# Liion-Tester.net
KiCad netlist of a schematic drawn in EAGLE
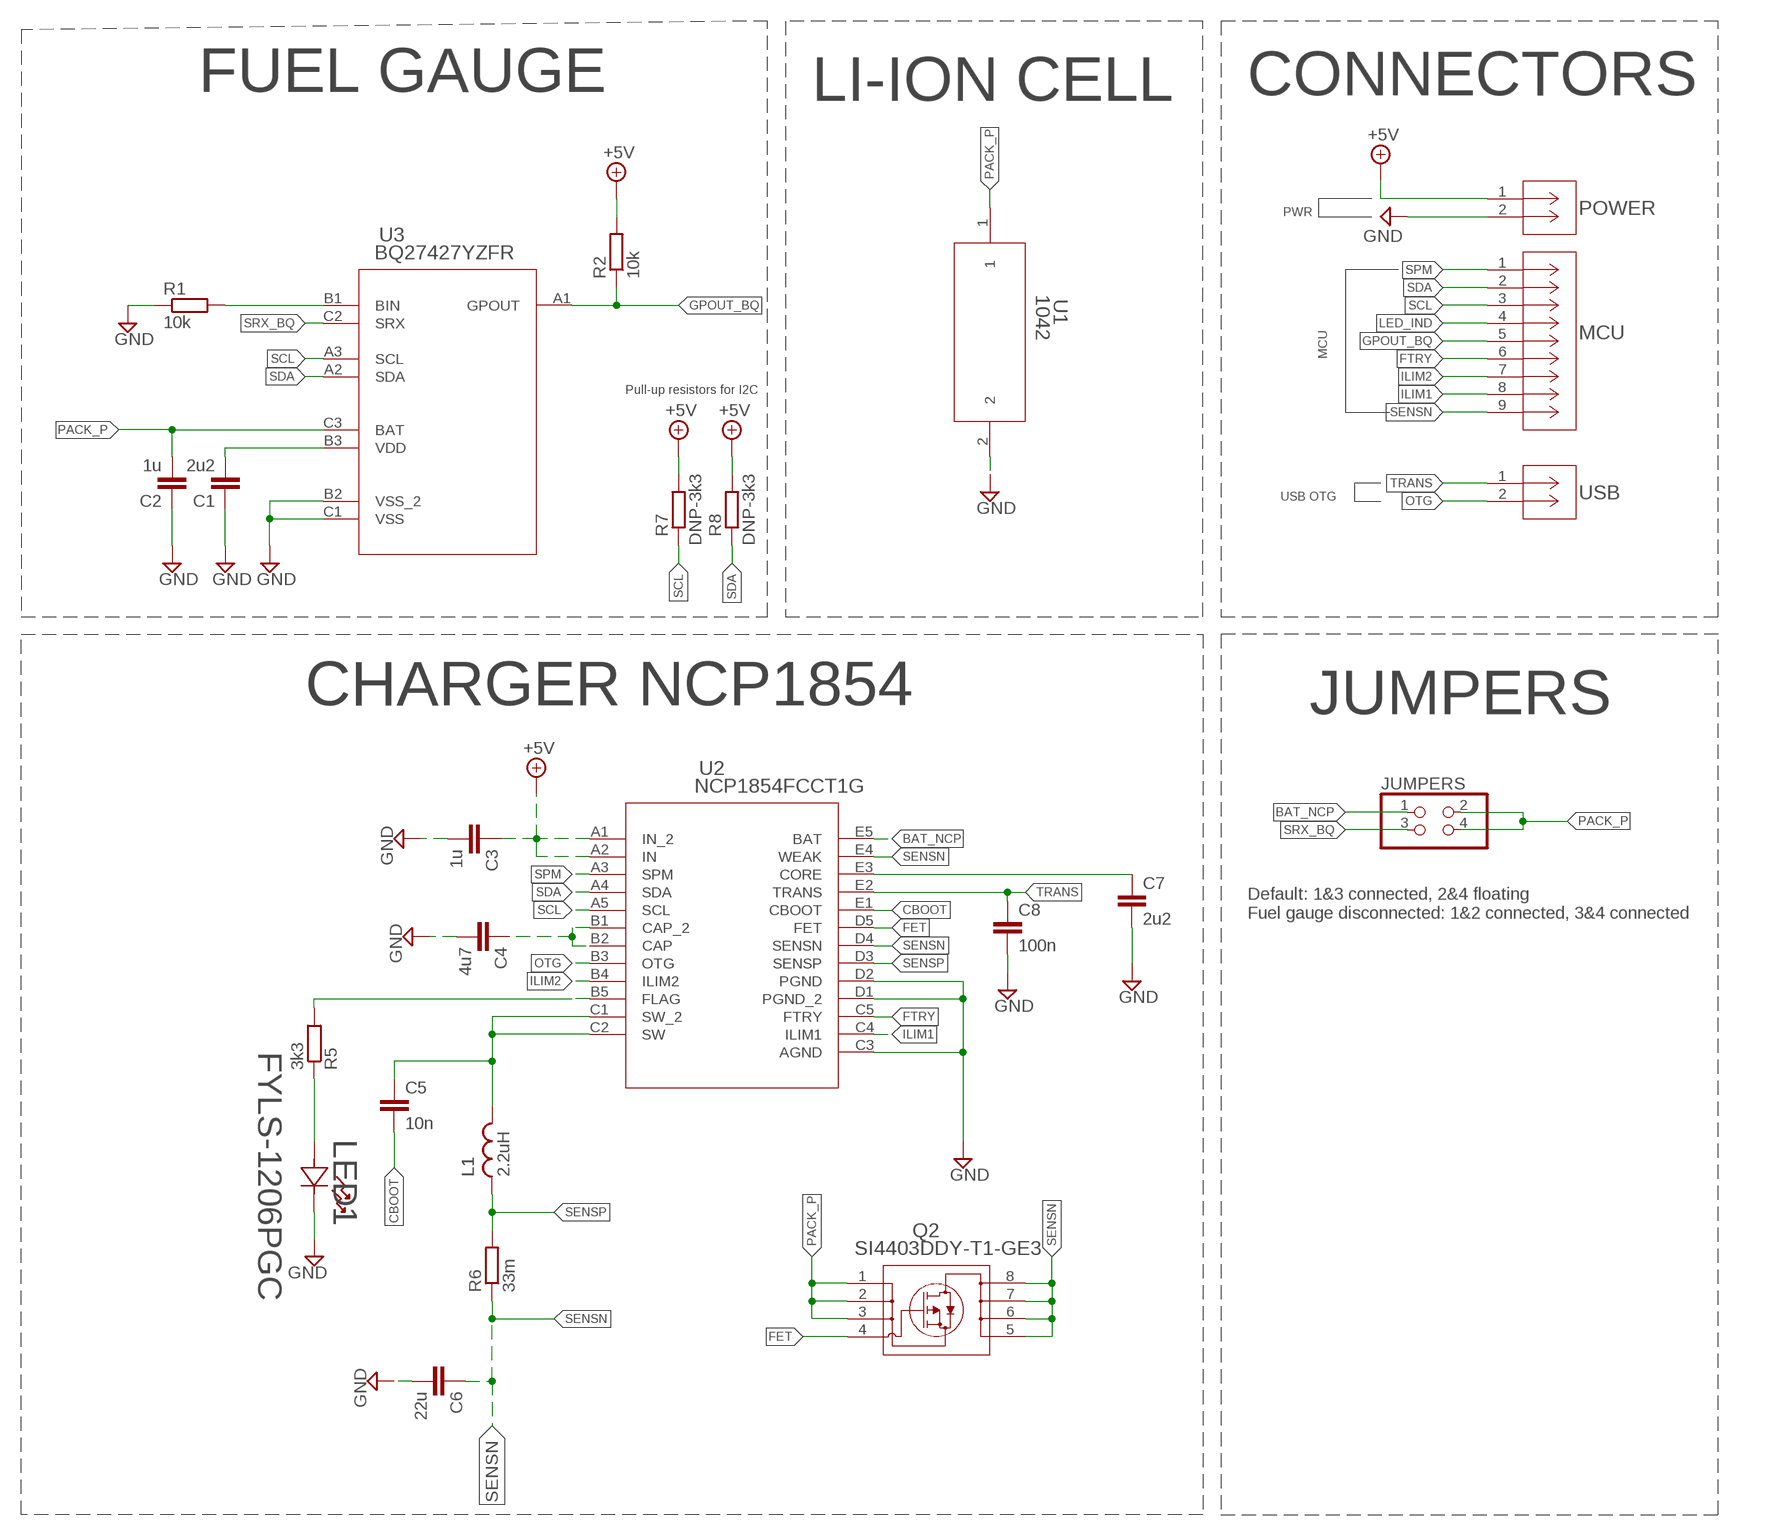
[diagram p0: schematic, sheet 1]

(export (version "E")
  (design (tool "Eeschema 10.0.6"))
  (components
    (comp (ref "C1")
      (value "2u2")
      (footprint "eagle-import:C0603")
      (libsource (lib "eagle-import") (part "C-EUC0603"))
    )
    (comp (ref "C2")
      (value "1u")
      (footprint "eagle-import:C0603")
      (libsource (lib "eagle-import") (part "C-EUC0603"))
    )
    (comp (ref "C3")
      (value "1u")
      (footprint "eagle-import:C0603")
      (libsource (lib "eagle-import") (part "C-EUC0603"))
    )
    (comp (ref "C4")
      (value "4u7")
      (footprint "eagle-import:C0603")
      (libsource (lib "eagle-import") (part "C-EUC0603"))
    )
    (comp (ref "C5")
      (value "10n")
      (footprint "eagle-import:C0603")
      (libsource (lib "eagle-import") (part "C-EUC0603"))
    )
    (comp (ref "C6")
      (value "22u")
      (footprint "eagle-import:C0603")
      (libsource (lib "eagle-import") (part "C-EUC0603"))
    )
    (comp (ref "C7")
      (value "2u2")
      (footprint "eagle-import:C0603")
      (libsource (lib "eagle-import") (part "C-EUC0603"))
    )
    (comp (ref "C8")
      (value "100n")
      (footprint "eagle-import:C0603")
      (libsource (lib "eagle-import") (part "C-EUC0603"))
    )
    (comp (ref "JUMPERS")
      (value "PINHD-2X2")
      (footprint "eagle-import:2X02")
      (libsource (lib "eagle-import") (part "PINHD-2X2"))
    )
    (comp (ref "L1")
      (value "2.2uH")
      (footprint "eagle-import:SPM3012T-2R2M-LR")
      (libsource (lib "eagle-import") (part "SPM3012T-2R2M-LR"))
    )
    (comp (ref "LED1")
      (value "FYLS-1206PGC")
      (footprint "eagle-import:LED_QBLP650_1206_QTB")
      (fields
        (field (name "MANUFACTURER_PART_NUMBER") "QBLP650-IW")
        (field (name "COPYRIGHT") "Copyright (C) 2024 Ultra Librarian. All rights reserved.")
      )
      (libsource (lib "eagle-import") (part "QBLP650-IW"))
    )
    (comp (ref "MCU")
      (value "250-109")
      (footprint "eagle-import:CONN_250-109_WAG")
      (fields (field (name "COPYRIGHT") "Copyright (C) 2024 Ultra Librarian. All rights reserved."))
      (libsource (lib "eagle-import") (part "250-109"))
    )
    (comp (ref "POWER")
      (value "250-102")
      (footprint "eagle-import:CONN_250-102_WAG")
      (fields (field (name "COPYRIGHT") "Copyright (C) 2024 Ultra Librarian. All rights reserved."))
      (libsource (lib "eagle-import") (part "250-102"))
    )
    (comp (ref "Q2")
      (value "SI4403DDY-T1-GE3")
      (footprint "eagle-import:SO-8_MS-012_VIS")
      (fields (field (name "COPYRIGHT") "Copyright (C) 2024 Ultra Librarian. All rights reserved."))
      (libsource (lib "eagle-import") (part "SI4403DDY-T1-GE3"))
    )
    (comp (ref "R1")
      (value "10k")
      (footprint "eagle-import:R0603")
      (libsource (lib "eagle-import") (part "R-EU_R0603"))
    )
    (comp (ref "R2")
      (value "10k")
      (footprint "eagle-import:R0603")
      (libsource (lib "eagle-import") (part "R-EU_R0603"))
    )
    (comp (ref "R5")
      (value "3k3")
      (footprint "eagle-import:R0603")
      (libsource (lib "eagle-import") (part "R-EU_R0603"))
    )
    (comp (ref "R6")
      (value "33m")
      (footprint "eagle-import:R2512")
      (libsource (lib "eagle-import") (part "R-EU_R2512"))
    )
    (comp (ref "R7")
      (value "DNP-3k3")
      (footprint "eagle-import:R0603")
      (libsource (lib "eagle-import") (part "R-EU_R0603"))
    )
    (comp (ref "R8")
      (value "DNP-3k3")
      (footprint "eagle-import:R0603")
      (libsource (lib "eagle-import") (part "R-EU_R0603"))
    )
    (comp (ref "U1")
      (value "1042")
      (footprint "eagle-import:1042_KEY")
      (fields (field (name "COPYRIGHT") "Copyright (C) 2024 Ultra Librarian. All rights reserved."))
      (libsource (lib "eagle-import") (part "1042"))
    )
    (comp (ref "U2")
      (value "NCP1854FCCT1G")
      (footprint "eagle-import:BGA25_2P55X2P2_ONS")
      (fields (field (name "COPYRIGHT") "Copyright (C) 2024 Ultra Librarian. All rights reserved."))
      (libsource (lib "eagle-import") (part "NCP1854FCCT1G"))
    )
    (comp (ref "U3")
      (value "BQ27427YZFR")
      (footprint "eagle-import:DSBGA9-YZF_TEX")
      (fields (field (name "COPYRIGHT") "Copyright (C) 2024 Ultra Librarian. All rights reserved."))
      (libsource (lib "eagle-import") (part "BQ27427YZFR"))
    )
    (comp (ref "USB")
      (value "250-102")
      (footprint "eagle-import:CONN_250-102_WAG")
      (fields (field (name "COPYRIGHT") "Copyright (C) 2024 Ultra Librarian. All rights reserved."))
      (libsource (lib "eagle-import") (part "250-102"))
    )
  )
  (nets
    (net (code "1") (name "+5V") (class "Default")
      (node (ref "C3") (pin "1") (pinfunction "1_1") (pintype "passive"))
      (node (ref "POWER") (pin "1") (pinfunction "1_1") (pintype "passive"))
      (node (ref "R2") (pin "2") (pinfunction "2_2") (pintype "passive"))
      (node (ref "R7") (pin "2") (pinfunction "2_2") (pintype "passive"))
      (node (ref "R8") (pin "2") (pinfunction "2_2") (pintype "passive"))
      (node (ref "U2") (pin "A1") (pinfunction "IN_2_A1") (pintype "input"))
      (node (ref "U2") (pin "A2") (pinfunction "IN_A2") (pintype "input"))
    )
    (net (code "2") (name "BAT_NCP") (class "Default")
      (node (ref "JUMPERS") (pin "1") (pinfunction "1_1") (pintype "passive"))
      (node (ref "U2") (pin "E5") (pinfunction "BAT_E5") (pintype "input"))
    )
    (net (code "3") (name "CBOOT") (class "Default")
      (node (ref "C5") (pin "2") (pinfunction "2_2") (pintype "passive"))
      (node (ref "U2") (pin "E1") (pinfunction "CBOOT_E1") (pintype "bidirectional"))
    )
    (net (code "4") (name "FET") (class "Default")
      (node (ref "Q2") (pin "4") (pinfunction "4_4") (pintype "passive"))
      (node (ref "U2") (pin "D5") (pinfunction "FET_D5") (pintype "output"))
    )
    (net (code "5") (name "FTRY") (class "Default")
      (node (ref "MCU") (pin "6") (pinfunction "6_6") (pintype "passive"))
      (node (ref "U2") (pin "C5") (pinfunction "FTRY_C5") (pintype "input"))
    )
    (net (code "6") (name "GND") (class "Default")
      (node (ref "C1") (pin "1") (pinfunction "1_1") (pintype "passive"))
      (node (ref "C2") (pin "1") (pinfunction "1_1") (pintype "passive"))
      (node (ref "C3") (pin "2") (pinfunction "2_2") (pintype "passive"))
      (node (ref "C4") (pin "2") (pinfunction "2_2") (pintype "passive"))
      (node (ref "C6") (pin "2") (pinfunction "2_2") (pintype "passive"))
      (node (ref "C7") (pin "2") (pinfunction "2_2") (pintype "passive"))
      (node (ref "C8") (pin "2") (pinfunction "2_2") (pintype "passive"))
      (node (ref "LED1") (pin "1") (pinfunction "CATHODE_1") (pintype "passive"))
      (node (ref "POWER") (pin "2") (pinfunction "2_2") (pintype "passive"))
      (node (ref "R1") (pin "1") (pinfunction "1_1") (pintype "passive"))
      (node (ref "U1") (pin "2") (pinfunction "2_2") (pintype "passive"))
      (node (ref "U2") (pin "C3") (pinfunction "AGND_C3") (pintype "power_in"))
      (node (ref "U2") (pin "D1") (pinfunction "PGND_2_D1") (pintype "power_in"))
      (node (ref "U2") (pin "D2") (pinfunction "PGND_D2") (pintype "power_in"))
      (node (ref "U3") (pin "B2") (pinfunction "VSS_2_B2") (pintype "passive"))
      (node (ref "U3") (pin "C1") (pinfunction "VSS_C1") (pintype "passive"))
    )
    (net (code "7") (name "GPOUT_BQ") (class "Default")
      (node (ref "MCU") (pin "5") (pinfunction "5_5") (pintype "passive"))
      (node (ref "R2") (pin "1") (pinfunction "1_1") (pintype "passive"))
      (node (ref "U3") (pin "A1") (pinfunction "GPOUT_A1") (pintype "output"))
    )
    (net (code "8") (name "ILIM1") (class "Default")
      (node (ref "MCU") (pin "8") (pinfunction "8_8") (pintype "passive"))
      (node (ref "U2") (pin "C4") (pinfunction "ILIM1_C4") (pintype "input"))
    )
    (net (code "9") (name "ILIM2") (class "Default")
      (node (ref "MCU") (pin "7") (pinfunction "7_7") (pintype "passive"))
      (node (ref "U2") (pin "B4") (pinfunction "ILIM2_B4") (pintype "input"))
    )
    (net (code "10") (name "LED_IND") (class "Default")
      (node (ref "MCU") (pin "4") (pinfunction "4_4") (pintype "passive"))
      (node (ref "R5") (pin "2") (pinfunction "2_2") (pintype "passive"))
      (node (ref "U2") (pin "B5") (pinfunction "FLAG_B5") (pintype "output"))
    )
    (net (code "11") (name "Net-(L1-2)") (class "Default")
      (node (ref "C5") (pin "1") (pinfunction "1_1") (pintype "passive"))
      (node (ref "L1") (pin "P$2") (pinfunction "2_P$2") (pintype "passive"))
      (node (ref "U2") (pin "C1") (pinfunction "SW_2_C1") (pintype "output"))
      (node (ref "U2") (pin "C2") (pinfunction "SW_C2") (pintype "output"))
    )
    (net (code "12") (name "Net-(LED1-ANODE)") (class "Default")
      (node (ref "LED1") (pin "2") (pinfunction "ANODE_2") (pintype "passive"))
      (node (ref "R5") (pin "1") (pinfunction "1_1") (pintype "passive"))
    )
    (net (code "13") (name "Net-(U2-CAP)") (class "Default")
      (node (ref "C4") (pin "1") (pinfunction "1_1") (pintype "passive"))
      (node (ref "U2") (pin "B1") (pinfunction "CAP_2_B1") (pintype "passive"))
      (node (ref "U2") (pin "B2") (pinfunction "CAP_B2") (pintype "passive"))
    )
    (net (code "14") (name "Net-(U2-CORE)") (class "Default")
      (node (ref "C7") (pin "1") (pinfunction "1_1") (pintype "passive"))
      (node (ref "U2") (pin "E3") (pinfunction "CORE_E3") (pintype "output"))
    )
    (net (code "15") (name "Net-(U3-BIN)") (class "Default")
      (node (ref "R1") (pin "2") (pinfunction "2_2") (pintype "passive"))
      (node (ref "U3") (pin "B1") (pinfunction "BIN_B1") (pintype "input"))
    )
    (net (code "16") (name "Net-(U3-VDD)") (class "Default")
      (node (ref "C1") (pin "2") (pinfunction "2_2") (pintype "passive"))
      (node (ref "U3") (pin "B3") (pinfunction "VDD_B3") (pintype "output"))
    )
    (net (code "17") (name "OTG") (class "Default")
      (node (ref "U2") (pin "B3") (pinfunction "OTG_B3") (pintype "input"))
      (node (ref "USB") (pin "2") (pinfunction "2_2") (pintype "passive"))
    )
    (net (code "18") (name "PACK_P") (class "Default")
      (node (ref "C2") (pin "2") (pinfunction "2_2") (pintype "passive"))
      (node (ref "JUMPERS") (pin "2") (pinfunction "2_2") (pintype "passive"))
      (node (ref "JUMPERS") (pin "4") (pinfunction "4_4") (pintype "passive"))
      (node (ref "Q2") (pin "1") (pinfunction "1_1") (pintype "passive"))
      (node (ref "Q2") (pin "2") (pinfunction "2_2") (pintype "passive"))
      (node (ref "Q2") (pin "3") (pinfunction "3_3") (pintype "passive"))
      (node (ref "U1") (pin "1") (pinfunction "1_1") (pintype "passive"))
      (node (ref "U3") (pin "C3") (pinfunction "BAT_C3") (pintype "power_in"))
    )
    (net (code "19") (name "SCL") (class "Default")
      (node (ref "MCU") (pin "3") (pinfunction "3_3") (pintype "passive"))
      (node (ref "R7") (pin "1") (pinfunction "1_1") (pintype "passive"))
      (node (ref "U2") (pin "A5") (pinfunction "SCL_A5") (pintype "input"))
      (node (ref "U3") (pin "A3") (pinfunction "SCL_A3") (pintype "bidirectional"))
    )
    (net (code "20") (name "SDA") (class "Default")
      (node (ref "MCU") (pin "2") (pinfunction "2_2") (pintype "passive"))
      (node (ref "R8") (pin "1") (pinfunction "1_1") (pintype "passive"))
      (node (ref "U2") (pin "A4") (pinfunction "SDA_A4") (pintype "bidirectional"))
      (node (ref "U3") (pin "A2") (pinfunction "SDA_A2") (pintype "bidirectional"))
    )
    (net (code "21") (name "SENSN") (class "Default")
      (node (ref "C6") (pin "1") (pinfunction "1_1") (pintype "passive"))
      (node (ref "MCU") (pin "9") (pinfunction "9_9") (pintype "passive"))
      (node (ref "Q2") (pin "5") (pinfunction "5_5") (pintype "passive"))
      (node (ref "Q2") (pin "6") (pinfunction "6_6") (pintype "passive"))
      (node (ref "Q2") (pin "7") (pinfunction "7_7") (pintype "passive"))
      (node (ref "Q2") (pin "8") (pinfunction "8_8") (pintype "passive"))
      (node (ref "R6") (pin "1") (pinfunction "1_1") (pintype "passive"))
      (node (ref "U2") (pin "D4") (pinfunction "SENSN_D4") (pintype "input"))
      (node (ref "U2") (pin "E4") (pinfunction "WEAK_E4") (pintype "output"))
    )
    (net (code "22") (name "SENSP") (class "Default")
      (node (ref "L1") (pin "P$1") (pinfunction "1_P$1") (pintype "passive"))
      (node (ref "R6") (pin "2") (pinfunction "2_2") (pintype "passive"))
      (node (ref "U2") (pin "D3") (pinfunction "SENSP_D3") (pintype "input"))
    )
    (net (code "23") (name "SPM") (class "Default")
      (node (ref "MCU") (pin "1") (pinfunction "1_1") (pintype "passive"))
      (node (ref "U2") (pin "A3") (pinfunction "SPM_A3") (pintype "input"))
    )
    (net (code "24") (name "SRX_BQ") (class "Default")
      (node (ref "JUMPERS") (pin "3") (pinfunction "3_3") (pintype "passive"))
      (node (ref "U3") (pin "C2") (pinfunction "SRX_C2") (pintype "input"))
    )
    (net (code "25") (name "TRANS") (class "Default")
      (node (ref "C8") (pin "1") (pinfunction "1_1") (pintype "passive"))
      (node (ref "U2") (pin "E2") (pinfunction "TRANS_E2") (pintype "output"))
      (node (ref "USB") (pin "1") (pinfunction "1_1") (pintype "passive"))
    )
  )
)
